# Card_Edge_Connector.net
KiCad netlist of a schematic drawn in Altium Designer
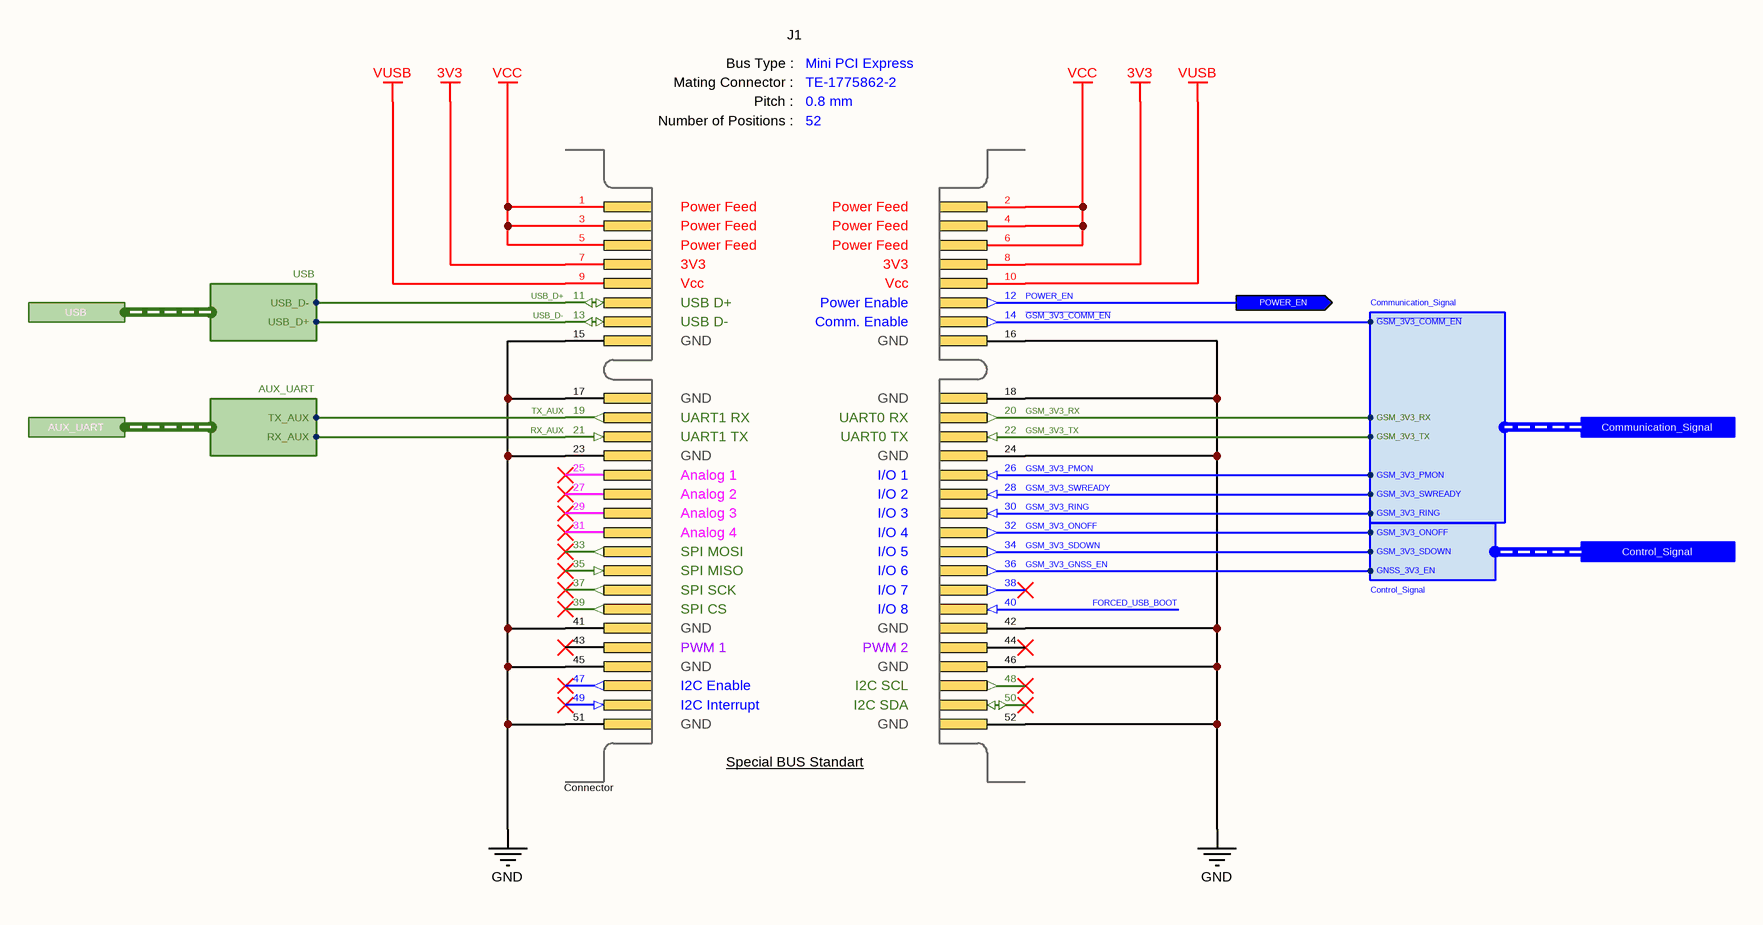
[diagram p0: Card Edge Connector.SchDoc]

(export (version "E")
  (design (tool "Eeschema 10.0.6"))
  (components
    (comp (ref "J1")
      (value "Connector - Mini PCI-E [Add-on]")
      (footprint "PCB - Mini PCI Express")
      (description "Mini PCI-Express gold finger connector.")
      (fields
        (field (name "BUS TYPE") "Mini PCI Express")
        (field (name "MATING CONNECTOR") "TE-1775862-2")
        (field (name "PITCH") "0.8 mm")
        (field (name "NUMBER OF POSITIONS") "52")
        (field (name "SYSTEM") "Connector")
      )
      (libsource (lib "P101DA_Library") (part "Connector - Mini PCI-E [Add-on]"))
    )
  )
  (nets
    (net (code "6") (name "/FORCED_USB_BOOT") (class "Default")
      (node (ref "J1") (pin "40") (pinfunction "Pin-40_40") (pintype "input"))
    )
    (net (code "7") (name "/GSM_3V3_GNSS_EN") (class "Default")
      (node (ref "J1") (pin "36") (pinfunction "Pin-36_36") (pintype "output"))
    )
    (net (code "8") (name "/GSM_3V3_ONOFF") (class "Default")
      (node (ref "J1") (pin "32") (pinfunction "Pin-32_32") (pintype "output"))
    )
    (net (code "9") (name "/GSM_3V3_PMON") (class "Default")
      (node (ref "J1") (pin "26") (pinfunction "Pin-26_26") (pintype "input"))
    )
    (net (code "10") (name "/GSM_3V3_RING") (class "Default")
      (node (ref "J1") (pin "30") (pinfunction "Pin-30_30") (pintype "input"))
    )
    (net (code "11") (name "/GSM_3V3_RX") (class "Default")
      (node (ref "J1") (pin "20") (pinfunction "Pin-20_20") (pintype "output"))
    )
    (net (code "12") (name "/GSM_3V3_SDOWN") (class "Default")
      (node (ref "J1") (pin "34") (pinfunction "Pin-34_34") (pintype "output"))
    )
    (net (code "13") (name "/GSM_3V3_SWREADY") (class "Default")
      (node (ref "J1") (pin "28") (pinfunction "Pin-28_28") (pintype "input"))
    )
    (net (code "14") (name "/GSM_3V3_TX") (class "Default")
      (node (ref "J1") (pin "22") (pinfunction "Pin-22_22") (pintype "input"))
    )
    (net (code "15") (name "/POWER_EN") (class "Default")
      (node (ref "J1") (pin "12") (pinfunction "Pin-12_12") (pintype "output"))
    )
    (net (code "16") (name "/RX_AUX") (class "Default")
      (node (ref "J1") (pin "21") (pinfunction "Pin-21_21") (pintype "input"))
    )
    (net (code "17") (name "/TX_AUX") (class "Default")
      (node (ref "J1") (pin "19") (pinfunction "Pin-19_19") (pintype "output"))
    )
    (net (code "18") (name "/USB_D+") (class "Default")
      (node (ref "J1") (pin "11") (pinfunction "Pin-11_11") (pintype "bidirectional"))
    )
    (net (code "19") (name "/USB_D-") (class "Default")
      (node (ref "J1") (pin "13") (pinfunction "Pin-13_13") (pintype "bidirectional"))
    )
    (net (code "23") (name "/~{GSM_3V3_COMM_EN}") (class "Default")
      (node (ref "J1") (pin "14") (pinfunction "Pin-14_14") (pintype "output"))
    )
    (net (code "24") (name "3V3") (class "Default")
      (node (ref "J1") (pin "7") (pinfunction "Pin-7_7") (pintype "power_in"))
      (node (ref "J1") (pin "8") (pinfunction "Pin-8_8") (pintype "power_in"))
    )
    (net (code "25") (name "GND") (class "Default")
      (node (ref "J1") (pin "15") (pinfunction "Pin-15_15") (pintype "power_in"))
      (node (ref "J1") (pin "16") (pinfunction "Pin-16_16") (pintype "power_in"))
      (node (ref "J1") (pin "17") (pinfunction "Pin-17_17") (pintype "power_in"))
      (node (ref "J1") (pin "18") (pinfunction "Pin-18_18") (pintype "power_in"))
      (node (ref "J1") (pin "23") (pinfunction "Pin-23_23") (pintype "power_in"))
      (node (ref "J1") (pin "24") (pinfunction "Pin-24_24") (pintype "power_in"))
      (node (ref "J1") (pin "41") (pinfunction "Pin-41_41") (pintype "power_in"))
      (node (ref "J1") (pin "42") (pinfunction "Pin-42_42") (pintype "power_in"))
      (node (ref "J1") (pin "45") (pinfunction "Pin-45_45") (pintype "power_in"))
      (node (ref "J1") (pin "46") (pinfunction "Pin-46_46") (pintype "power_in"))
      (node (ref "J1") (pin "51") (pinfunction "Pin-51_51") (pintype "power_in"))
      (node (ref "J1") (pin "52") (pinfunction "Pin-52_52") (pintype "power_in"))
    )
    (net (code "26") (name "VCC") (class "Default")
      (node (ref "J1") (pin "1") (pinfunction "Pin-1_1") (pintype "power_in"))
      (node (ref "J1") (pin "2") (pinfunction "Pin-2_2") (pintype "power_in"))
      (node (ref "J1") (pin "3") (pinfunction "Pin-3_3") (pintype "power_in"))
      (node (ref "J1") (pin "4") (pinfunction "Pin-4_4") (pintype "power_in"))
      (node (ref "J1") (pin "5") (pinfunction "Pin-5_5") (pintype "power_in"))
      (node (ref "J1") (pin "6") (pinfunction "Pin-6_6") (pintype "power_in"))
    )
    (net (code "27") (name "VUSB") (class "Default")
      (node (ref "J1") (pin "10") (pinfunction "Pin-10_10") (pintype "power_in"))
      (node (ref "J1") (pin "9") (pinfunction "Pin-9_9") (pintype "power_in"))
    )
    (net (code "28") (name "unconnected-(J1-Pin-25-Pad25)") (class "Default")
      (node (ref "J1") (pin "25") (pinfunction "Pin-25_25") (pintype "passive+no_connect"))
    )
    (net (code "29") (name "unconnected-(J1-Pin-27-Pad27)") (class "Default")
      (node (ref "J1") (pin "27") (pinfunction "Pin-27_27") (pintype "passive+no_connect"))
    )
    (net (code "30") (name "unconnected-(J1-Pin-29-Pad29)") (class "Default")
      (node (ref "J1") (pin "29") (pinfunction "Pin-29_29") (pintype "passive+no_connect"))
    )
    (net (code "31") (name "unconnected-(J1-Pin-31-Pad31)") (class "Default")
      (node (ref "J1") (pin "31") (pinfunction "Pin-31_31") (pintype "passive+no_connect"))
    )
    (net (code "32") (name "unconnected-(J1-Pin-33-Pad33)") (class "Default")
      (node (ref "J1") (pin "33") (pinfunction "Pin-33_33") (pintype "output+no_connect"))
    )
    (net (code "33") (name "unconnected-(J1-Pin-35-Pad35)") (class "Default")
      (node (ref "J1") (pin "35") (pinfunction "Pin-35_35") (pintype "input+no_connect"))
    )
    (net (code "34") (name "unconnected-(J1-Pin-37-Pad37)") (class "Default")
      (node (ref "J1") (pin "37") (pinfunction "Pin-37_37") (pintype "output+no_connect"))
    )
    (net (code "35") (name "unconnected-(J1-Pin-38-Pad38)") (class "Default")
      (node (ref "J1") (pin "38") (pinfunction "Pin-38_38") (pintype "output+no_connect"))
    )
    (net (code "36") (name "unconnected-(J1-Pin-39-Pad39)") (class "Default")
      (node (ref "J1") (pin "39") (pinfunction "Pin-39_39") (pintype "output+no_connect"))
    )
    (net (code "37") (name "unconnected-(J1-Pin-43-Pad43)") (class "Default")
      (node (ref "J1") (pin "43") (pinfunction "Pin-43_43") (pintype "passive+no_connect"))
    )
    (net (code "38") (name "unconnected-(J1-Pin-44-Pad44)") (class "Default")
      (node (ref "J1") (pin "44") (pinfunction "Pin-44_44") (pintype "passive+no_connect"))
    )
    (net (code "39") (name "unconnected-(J1-Pin-47-Pad47)") (class "Default")
      (node (ref "J1") (pin "47") (pinfunction "Pin-47_47") (pintype "output+no_connect"))
    )
    (net (code "40") (name "unconnected-(J1-Pin-48-Pad48)") (class "Default")
      (node (ref "J1") (pin "48") (pinfunction "Pin-48_48") (pintype "output+no_connect"))
    )
    (net (code "41") (name "unconnected-(J1-Pin-49-Pad49)") (class "Default")
      (node (ref "J1") (pin "49") (pinfunction "Pin-49_49") (pintype "input+no_connect"))
    )
    (net (code "42") (name "unconnected-(J1-Pin-50-Pad50)") (class "Default")
      (node (ref "J1") (pin "50") (pinfunction "Pin-50_50") (pintype "bidirectional+no_connect"))
    )
  )
)
